# eeZee555.net
KiCad netlist of a schematic drawn in EAGLE
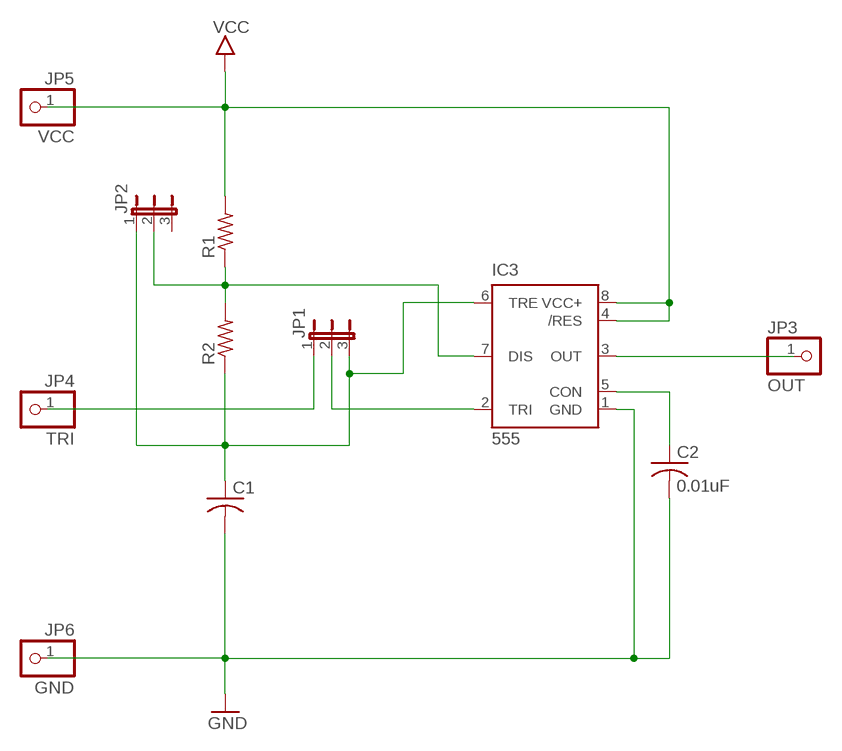
[diagram p0: schematic, sheet 1]

(export (version "E")
  (design (tool "Eeschema 10.0.6"))
  (components
    (comp (ref "C1")
      (value "C-US050-025X075")
      (footprint "eagle-import:C050-025X075")
      (libsource (lib "eagle-import") (part "C-US050-025X075"))
    )
    (comp (ref "C2")
      (value "0.01uF")
      (footprint "eagle-import:C0603")
      (libsource (lib "eagle-import") (part "C-USC0603"))
    )
    (comp (ref "IC3")
      (value "555")
      (footprint "eagle-import:DIL-08")
      (fields (field (name "MF") "Arrow Electronics") (field (name "MPN") "NE555N"))
      (libsource (lib "eagle-import") (part "NE555P"))
    )
    (comp (ref "JP1")
      (value "JP2E")
      (footprint "eagle-import:JP2")
      (libsource (lib "eagle-import") (part "JP2E"))
    )
    (comp (ref "JP2")
      (value "JP2E")
      (footprint "eagle-import:JP2")
      (libsource (lib "eagle-import") (part "JP2E"))
    )
    (comp (ref "JP3")
      (value "OUT")
      (footprint "eagle-import:1X01-S")
      (libsource (lib "eagle-import") (part "PINHD-1X01_2.54-S"))
    )
    (comp (ref "JP4")
      (value "TRI")
      (footprint "eagle-import:1X01-S")
      (libsource (lib "eagle-import") (part "PINHD-1X01_2.54-S"))
    )
    (comp (ref "JP5")
      (value "VCC")
      (footprint "eagle-import:1X01-S")
      (libsource (lib "eagle-import") (part "PINHD-1X01_2.54-S"))
    )
    (comp (ref "JP6")
      (value "GND")
      (footprint "eagle-import:1X01-S")
      (libsource (lib "eagle-import") (part "PINHD-1X01_2.54-S"))
    )
    (comp (ref "R1")
      (value "R-US_0204/5")
      (footprint "eagle-import:0204_5")
      (libsource (lib "eagle-import") (part "R-US_0204/5"))
    )
    (comp (ref "R2")
      (value "R-US_0204/5")
      (footprint "eagle-import:0204_5")
      (libsource (lib "eagle-import") (part "R-US_0204/5"))
    )
  )
  (nets
    (net (code "1") (name "GND") (class "Default")
      (node (ref "C1") (pin "2") (pinfunction "2_2") (pintype "passive"))
      (node (ref "C2") (pin "2") (pinfunction "2_2") (pintype "passive"))
      (node (ref "IC3") (pin "1") (pinfunction "GND_1") (pintype "power_in"))
      (node (ref "JP6") (pin "1") (pinfunction "1_1") (pintype "passive"))
    )
    (net (code "2") (name "Net-(IC3-CON)") (class "Default")
      (node (ref "C2") (pin "1") (pinfunction "1_1") (pintype "passive"))
      (node (ref "IC3") (pin "5") (pinfunction "CON_5") (pintype "input"))
    )
    (net (code "3") (name "Net-(IC3-DIS)") (class "Default")
      (node (ref "IC3") (pin "7") (pinfunction "DIS_7") (pintype "input"))
      (node (ref "JP2") (pin "2") (pinfunction "2_2") (pintype "passive"))
      (node (ref "R1") (pin "1") (pinfunction "1_1") (pintype "passive"))
      (node (ref "R2") (pin "2") (pinfunction "2_2") (pintype "passive"))
    )
    (net (code "4") (name "Net-(IC3-OUT)") (class "Default")
      (node (ref "IC3") (pin "3") (pinfunction "OUT_3") (pintype "output"))
      (node (ref "JP3") (pin "1") (pinfunction "1_1") (pintype "passive"))
    )
    (net (code "5") (name "Net-(IC3-TRE)") (class "Default")
      (node (ref "C1") (pin "1") (pinfunction "1_1") (pintype "passive"))
      (node (ref "IC3") (pin "6") (pinfunction "TRE_6") (pintype "input"))
      (node (ref "JP1") (pin "3") (pinfunction "3_3") (pintype "passive"))
      (node (ref "JP2") (pin "1") (pinfunction "1_1") (pintype "passive"))
      (node (ref "R2") (pin "1") (pinfunction "1_1") (pintype "passive"))
    )
    (net (code "6") (name "Net-(IC3-TRI)") (class "Default")
      (node (ref "IC3") (pin "2") (pinfunction "TRI_2") (pintype "input"))
      (node (ref "JP1") (pin "2") (pinfunction "2_2") (pintype "passive"))
    )
    (net (code "7") (name "Net-(JP1-Pad1)") (class "Default")
      (node (ref "JP1") (pin "1") (pinfunction "1_1") (pintype "passive"))
      (node (ref "JP4") (pin "1") (pinfunction "1_1") (pintype "passive"))
    )
    (net (code "8") (name "VCC") (class "Default")
      (node (ref "IC3") (pin "4") (pinfunction "/RES_4") (pintype "input"))
      (node (ref "IC3") (pin "8") (pinfunction "VCC+_8") (pintype "power_in"))
      (node (ref "JP5") (pin "1") (pinfunction "1_1") (pintype "passive"))
      (node (ref "R1") (pin "2") (pinfunction "2_2") (pintype "passive"))
    )
    (net (code "9") (name "unconnected-(JP2-Pad3)") (class "Default")
      (node (ref "JP2") (pin "3") (pinfunction "3_3") (pintype "passive"))
    )
  )
)
